# CMRI-Bus-Interface-L.net
KiCad netlist of a schematic drawn in EAGLE
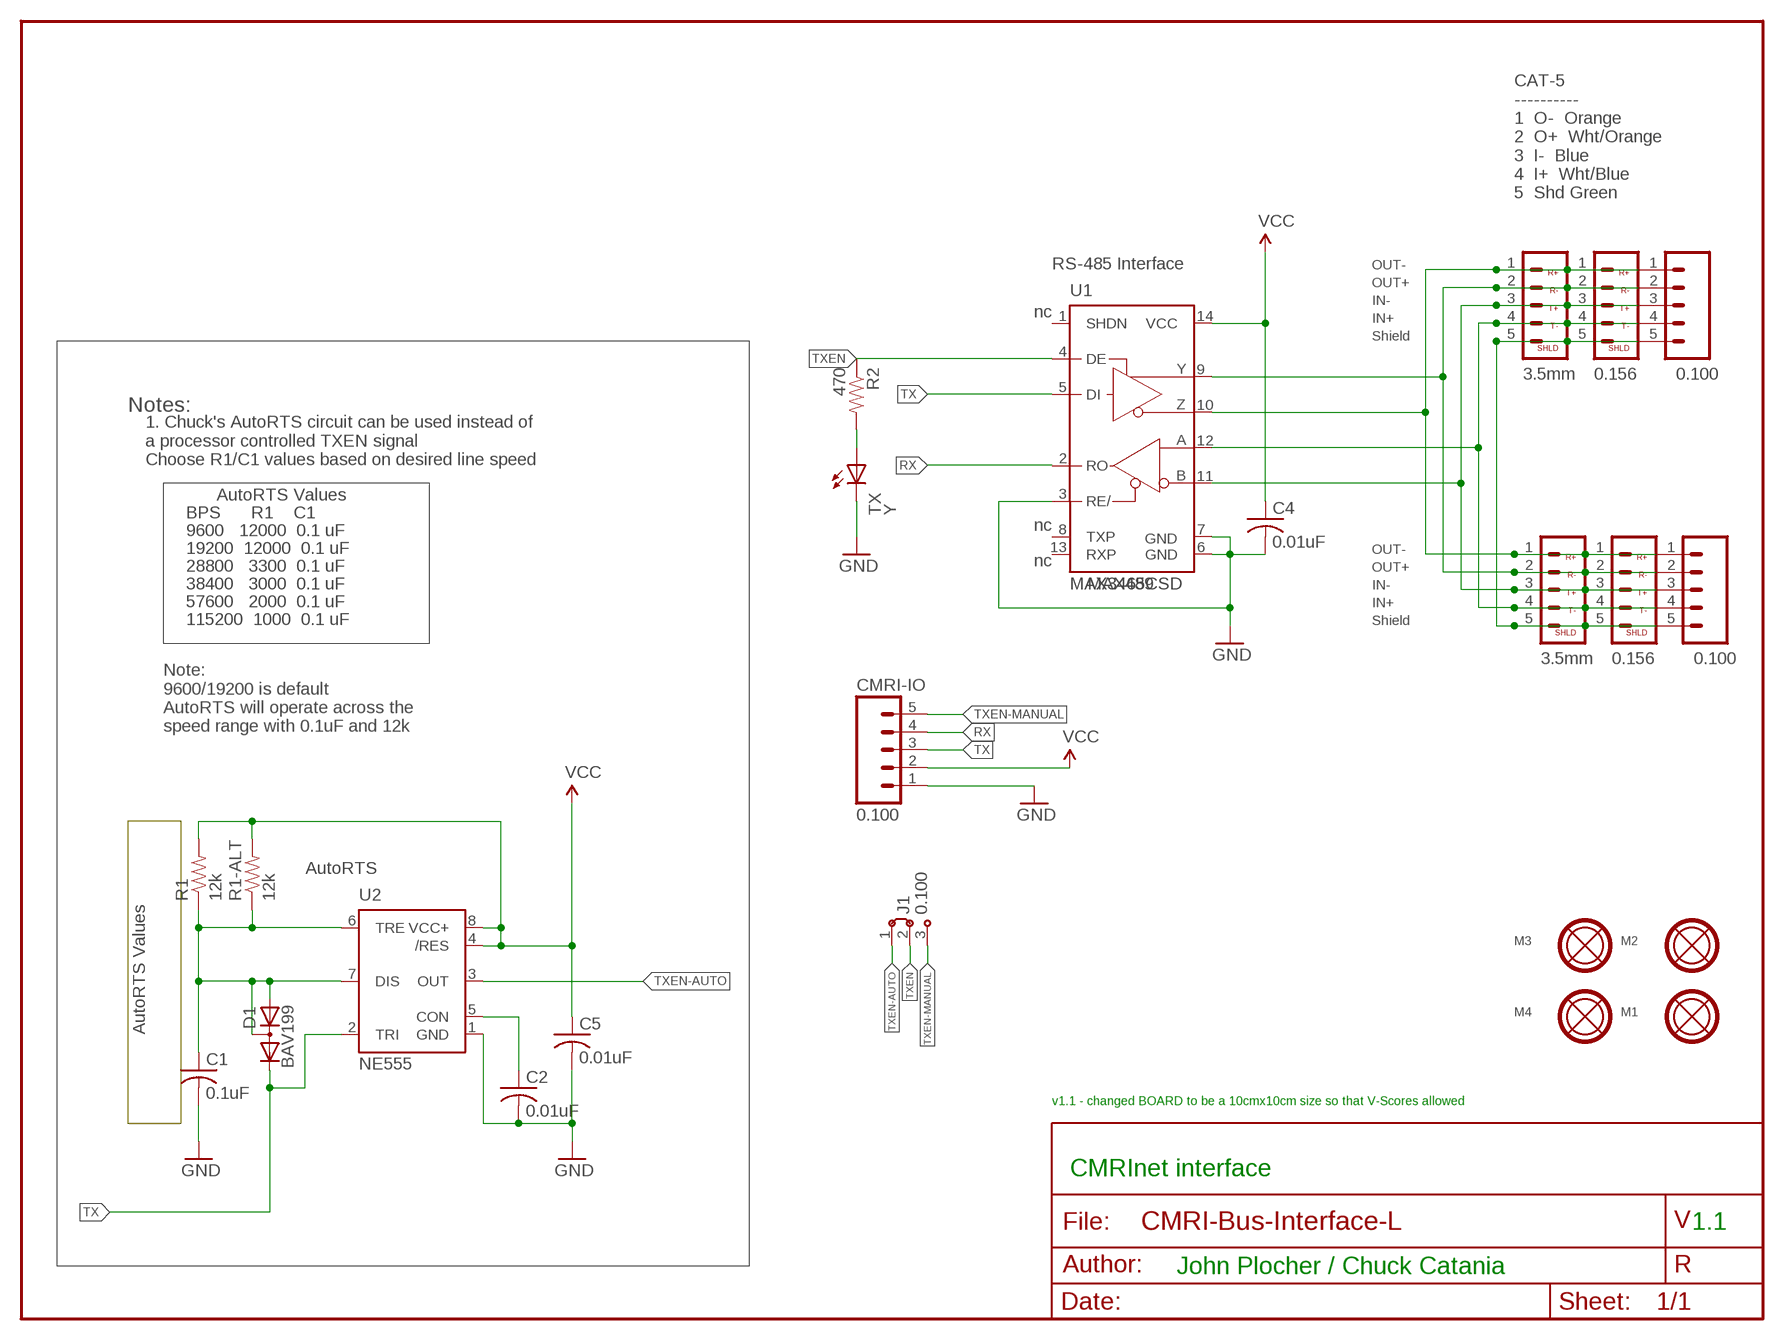
[diagram p0: schematic, sheet 1]

(export (version "E")
  (design (tool "Eeschema 10.0.6"))
  (components
    (comp (ref "C1")
      (value "0.1uF")
      (footprint "eagle-import:0603-CAP")
      (libsource (lib "eagle-import") (part "CAP0603"))
    )
    (comp (ref "C2")
      (value "0.01uF")
      (footprint "eagle-import:0603-CAP")
      (libsource (lib "eagle-import") (part "CAP0603"))
    )
    (comp (ref "C4")
      (value "0.01uF")
      (footprint "eagle-import:0603-CAP")
      (libsource (lib "eagle-import") (part "CAP0603"))
    )
    (comp (ref "C5")
      (value "0.01uF")
      (footprint "eagle-import:0603-CAP")
      (libsource (lib "eagle-import") (part "CAP0603"))
    )
    (comp (ref "CMRI-IO")
      (value "0.100")
      (footprint "eagle-import:1X05-CMRI-IO")
      (libsource (lib "eagle-import") (part "CONNECTOR-M05CMRI"))
    )
    (comp (ref "CMRINET1")
      (value "3.5mm")
      (footprint "eagle-import:CMRINET-3.5MM")
      (libsource (lib "eagle-import") (part "CONNECTOR-CMRINET3.5MM"))
    )
    (comp (ref "CMRINET2")
      (value "3.5mm")
      (footprint "eagle-import:CMRINET-3.5MM")
      (libsource (lib "eagle-import") (part "CONNECTOR-CMRINET3.5MM"))
    )
    (comp (ref "CMRINET3")
      (value "0.156")
      (footprint "eagle-import:KK-156-5")
      (libsource (lib "eagle-import") (part "CONNECTOR-CMRINET.156"))
    )
    (comp (ref "CMRINET4")
      (value "0.156")
      (footprint "eagle-import:KK-156-5")
      (libsource (lib "eagle-import") (part "CONNECTOR-CMRINET.156"))
    )
    (comp (ref "CON1")
      (value "0.100")
      (footprint "eagle-import:1X05_LOCK")
      (libsource (lib "eagle-import") (part "CONNECTOR-M05LOCK"))
    )
    (comp (ref "CON2")
      (value "0.100")
      (footprint "eagle-import:1X05_LOCK")
      (libsource (lib "eagle-import") (part "CONNECTOR-M05LOCK"))
    )
    (comp (ref "D1")
      (value "BAV199")
      (footprint "eagle-import:SOT23")
      (libsource (lib "eagle-import") (part "DIODE-BAV199"))
    )
    (comp (ref "J1")
      (value "0.100")
      (footprint "eagle-import:J3-254")
      (libsource (lib "eagle-import") (part "JUMPER-3-DEFAULT2.54MM"))
    )
    (comp (ref "M1")
      (value "MOUNTINGHOLE")
      (footprint "eagle-import:MOUNTINGHOLE")
      (libsource (lib "eagle-import") (part "MOUNTINGHOLE"))
    )
    (comp (ref "M2")
      (value "MOUNTINGHOLE")
      (footprint "eagle-import:MOUNTINGHOLE")
      (libsource (lib "eagle-import") (part "MOUNTINGHOLE"))
    )
    (comp (ref "M3")
      (value "MOUNTINGHOLE")
      (footprint "eagle-import:MOUNTINGHOLE")
      (libsource (lib "eagle-import") (part "MOUNTINGHOLE"))
    )
    (comp (ref "M4")
      (value "MOUNTINGHOLE")
      (footprint "eagle-import:MOUNTINGHOLE")
      (libsource (lib "eagle-import") (part "MOUNTINGHOLE"))
    )
    (comp (ref "R1")
      (value "12k")
      (footprint "eagle-import:AXIAL-0.4-RES")
      (libsource (lib "eagle-import") (part "RPTH04"))
    )
    (comp (ref "R1-ALT")
      (value "12k")
      (footprint "eagle-import:0805-RES")
      (libsource (lib "eagle-import") (part "R0805-RES"))
    )
    (comp (ref "R2")
      (value "470")
      (footprint "eagle-import:0805-RES")
      (libsource (lib "eagle-import") (part "R0805-RES"))
    )
    (comp (ref "TX")
      (value "Y")
      (footprint "eagle-import:0603-LED")
      (libsource (lib "eagle-import") (part "LED0603-LED"))
    )
    (comp (ref "U1")
      (value "MAX3465CSD")
      (footprint "eagle-import:SO14")
      (fields (field (name "MPN") "MAX3465CSD+"))
      (libsource (lib "eagle-import") (part "MAX346SD5C"))
    )
    (comp (ref "U2")
      (value "NE555")
      (footprint "eagle-import:SO08")
      (libsource (lib "eagle-import") (part "NE555D"))
    )
  )
  (nets
    (net (code "1") (name "GND") (class "Default")
      (node (ref "C1") (pin "2") (pinfunction "2_2") (pintype "passive"))
      (node (ref "C2") (pin "2") (pinfunction "2_2") (pintype "passive"))
      (node (ref "C4") (pin "2") (pinfunction "2_2") (pintype "passive"))
      (node (ref "C5") (pin "2") (pinfunction "2_2") (pintype "passive"))
      (node (ref "CMRI-IO") (pin "1") (pinfunction "1_1") (pintype "passive"))
      (node (ref "TX") (pin "C") (pinfunction "C_C") (pintype "passive"))
      (node (ref "U1") (pin "3") (pinfunction "RE/_3") (pintype "input"))
      (node (ref "U1") (pin "6") (pinfunction "GND_6") (pintype "power_in"))
      (node (ref "U1") (pin "7") (pinfunction "GND_7") (pintype "power_in"))
      (node (ref "U2") (pin "1") (pinfunction "GND_1") (pintype "power_in"))
    )
    (net (code "2") (name "Net-(CMRINET1-Pad5)") (class "Default")
      (node (ref "CMRINET1") (pin "5") (pinfunction "5_5") (pintype "passive"))
      (node (ref "CMRINET2") (pin "5") (pinfunction "5_5") (pintype "passive"))
      (node (ref "CMRINET3") (pin "5") (pinfunction "5_5") (pintype "passive"))
      (node (ref "CMRINET4") (pin "5") (pinfunction "5_5") (pintype "passive"))
      (node (ref "CON1") (pin "5") (pinfunction "5_5") (pintype "passive"))
      (node (ref "CON2") (pin "5") (pinfunction "5_5") (pintype "passive"))
    )
    (net (code "3") (name "Net-(D1-A)") (class "Default")
      (node (ref "C1") (pin "1") (pinfunction "1_1") (pintype "passive"))
      (node (ref "D1") (pin "1") (pinfunction "A_1") (pintype "passive"))
      (node (ref "D1") (pin "3") (pinfunction "AC_3") (pintype "passive"))
      (node (ref "R1") (pin "P$1") (pinfunction "1_P$1") (pintype "passive"))
      (node (ref "R1-ALT") (pin "1") (pinfunction "1_1") (pintype "passive"))
      (node (ref "U2") (pin "6") (pinfunction "TRE_6") (pintype "input"))
      (node (ref "U2") (pin "7") (pinfunction "DIS_7") (pintype "input"))
    )
    (net (code "4") (name "Net-(R2-Pad2)") (class "Default")
      (node (ref "R2") (pin "2") (pinfunction "2_2") (pintype "passive"))
      (node (ref "TX") (pin "A") (pinfunction "A_A") (pintype "passive"))
    )
    (net (code "5") (name "Net-(U1-A)") (class "Default")
      (node (ref "CMRINET1") (pin "4") (pinfunction "4_4") (pintype "passive"))
      (node (ref "CMRINET2") (pin "4") (pinfunction "4_4") (pintype "passive"))
      (node (ref "CMRINET3") (pin "4") (pinfunction "4_4") (pintype "passive"))
      (node (ref "CMRINET4") (pin "4") (pinfunction "4_4") (pintype "passive"))
      (node (ref "CON1") (pin "4") (pinfunction "4_4") (pintype "passive"))
      (node (ref "CON2") (pin "4") (pinfunction "4_4") (pintype "passive"))
      (node (ref "U1") (pin "12") (pinfunction "A_12") (pintype "input"))
    )
    (net (code "6") (name "Net-(U1-B)") (class "Default")
      (node (ref "CMRINET1") (pin "3") (pinfunction "3_3") (pintype "passive"))
      (node (ref "CMRINET2") (pin "3") (pinfunction "3_3") (pintype "passive"))
      (node (ref "CMRINET3") (pin "3") (pinfunction "3_3") (pintype "passive"))
      (node (ref "CMRINET4") (pin "3") (pinfunction "3_3") (pintype "passive"))
      (node (ref "CON1") (pin "3") (pinfunction "3_3") (pintype "passive"))
      (node (ref "CON2") (pin "3") (pinfunction "3_3") (pintype "passive"))
      (node (ref "U1") (pin "11") (pinfunction "B_11") (pintype "input"))
    )
    (net (code "7") (name "Net-(U1-Y)") (class "Default")
      (node (ref "CMRINET1") (pin "2") (pinfunction "2_2") (pintype "passive"))
      (node (ref "CMRINET2") (pin "2") (pinfunction "2_2") (pintype "passive"))
      (node (ref "CMRINET3") (pin "2") (pinfunction "2_2") (pintype "passive"))
      (node (ref "CMRINET4") (pin "2") (pinfunction "2_2") (pintype "passive"))
      (node (ref "CON1") (pin "2") (pinfunction "2_2") (pintype "passive"))
      (node (ref "CON2") (pin "2") (pinfunction "2_2") (pintype "passive"))
      (node (ref "U1") (pin "9") (pinfunction "Y_9") (pintype "output"))
    )
    (net (code "8") (name "Net-(U1-Z)") (class "Default")
      (node (ref "CMRINET1") (pin "1") (pinfunction "1_1") (pintype "passive"))
      (node (ref "CMRINET2") (pin "1") (pinfunction "1_1") (pintype "passive"))
      (node (ref "CMRINET3") (pin "1") (pinfunction "1_1") (pintype "passive"))
      (node (ref "CMRINET4") (pin "1") (pinfunction "1_1") (pintype "passive"))
      (node (ref "CON1") (pin "1") (pinfunction "1_1") (pintype "passive"))
      (node (ref "CON2") (pin "1") (pinfunction "1_1") (pintype "passive"))
      (node (ref "U1") (pin "10") (pinfunction "Z_10") (pintype "output"))
    )
    (net (code "9") (name "Net-(U2-CON)") (class "Default")
      (node (ref "C2") (pin "1") (pinfunction "1_1") (pintype "passive"))
      (node (ref "U2") (pin "5") (pinfunction "CON_5") (pintype "input"))
    )
    (net (code "10") (name "RX") (class "Default")
      (node (ref "CMRI-IO") (pin "4") (pinfunction "4_4") (pintype "passive"))
      (node (ref "U1") (pin "2") (pinfunction "RO_2") (pintype "output"))
    )
    (net (code "11") (name "TX") (class "Default")
      (node (ref "CMRI-IO") (pin "3") (pinfunction "3_3") (pintype "passive"))
      (node (ref "D1") (pin "2") (pinfunction "C_2") (pintype "passive"))
      (node (ref "U1") (pin "5") (pinfunction "DI_5") (pintype "input"))
      (node (ref "U2") (pin "2") (pinfunction "TRI_2") (pintype "input"))
    )
    (net (code "12") (name "TXEN") (class "Default")
      (node (ref "J1") (pin "2") (pinfunction "2_2") (pintype "passive"))
      (node (ref "R2") (pin "1") (pinfunction "1_1") (pintype "passive"))
      (node (ref "U1") (pin "4") (pinfunction "DE_4") (pintype "input"))
    )
    (net (code "13") (name "TXEN-AUTO") (class "Default")
      (node (ref "J1") (pin "1") (pinfunction "1_1") (pintype "passive"))
      (node (ref "U2") (pin "3") (pinfunction "OUT_3") (pintype "output"))
    )
    (net (code "14") (name "TXEN-MANUAL") (class "Default")
      (node (ref "CMRI-IO") (pin "5") (pinfunction "5_5") (pintype "passive"))
      (node (ref "J1") (pin "3") (pinfunction "3_3") (pintype "passive"))
    )
    (net (code "15") (name "VCC") (class "Default")
      (node (ref "C4") (pin "1") (pinfunction "1_1") (pintype "passive"))
      (node (ref "C5") (pin "1") (pinfunction "1_1") (pintype "passive"))
      (node (ref "CMRI-IO") (pin "2") (pinfunction "2_2") (pintype "passive"))
      (node (ref "R1") (pin "P$2") (pinfunction "2_P$2") (pintype "passive"))
      (node (ref "R1-ALT") (pin "2") (pinfunction "2_2") (pintype "passive"))
      (node (ref "U1") (pin "14") (pinfunction "VCC_14") (pintype "power_in"))
      (node (ref "U2") (pin "4") (pinfunction "/RES_4") (pintype "input"))
      (node (ref "U2") (pin "8") (pinfunction "VCC+_8") (pintype "power_in"))
    )
    (net (code "16") (name "unconnected-(U1-RXP-Pad13)") (class "Default")
      (node (ref "U1") (pin "13") (pinfunction "RXP_13") (pintype "passive"))
    )
    (net (code "17") (name "unconnected-(U1-SHDN-Pad1)") (class "Default")
      (node (ref "U1") (pin "1") (pinfunction "SHDN_1") (pintype "input"))
    )
    (net (code "18") (name "unconnected-(U1-TXP-Pad8)") (class "Default")
      (node (ref "U1") (pin "8") (pinfunction "TXP_8") (pintype "passive"))
    )
  )
)
